# MCU.net
KiCad netlist of a schematic drawn in Altium Designer
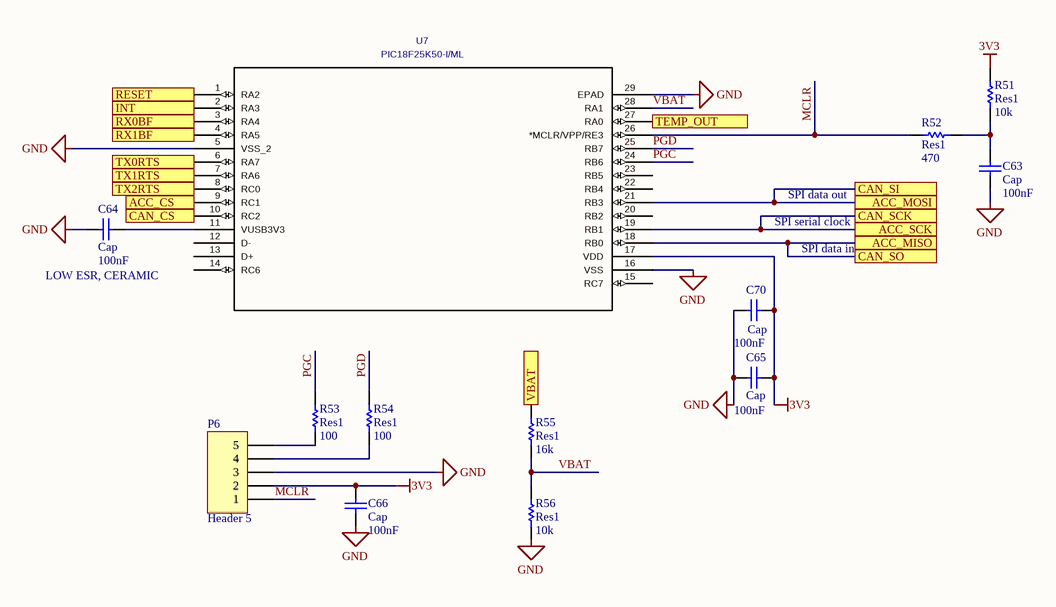
[diagram p0: MCU.SchDoc]

(export (version "E")
  (design (tool "Eeschema 10.0.6"))
  (components
    (comp (ref "C63")
      (value "Cap")
      (footprint "0402-A")
      (description "Capacitor")
      (fields (field (name "ALTIUM_VALUE") "100nF") (field (name "PUBLISHER") "Altium Limited"))
      (libsource (lib "Miscellaneous Devices") (part "Cap"))
    )
    (comp (ref "C64")
      (value "Cap")
      (footprint "0402-A")
      (description "Capacitor")
      (fields (field (name "ALTIUM_VALUE") "100nF") (field (name "PUBLISHER") "Altium Limited"))
      (libsource (lib "Miscellaneous Devices") (part "Cap"))
    )
    (comp (ref "C65")
      (value "Cap")
      (footprint "0402-A")
      (description "Capacitor")
      (fields (field (name "ALTIUM_VALUE") "100nF") (field (name "PUBLISHER") "Altium Limited"))
      (libsource (lib "Miscellaneous Devices") (part "Cap"))
    )
    (comp (ref "C66")
      (value "Cap")
      (footprint "0402-A")
      (description "Capacitor")
      (fields (field (name "ALTIUM_VALUE") "100nF") (field (name "PUBLISHER") "Altium Limited"))
      (libsource (lib "Miscellaneous Devices") (part "Cap"))
    )
    (comp (ref "C70")
      (value "Cap")
      (footprint "0402-A")
      (description "Capacitor")
      (fields (field (name "ALTIUM_VALUE") "100nF") (field (name "PUBLISHER") "Altium Limited"))
      (libsource (lib "Miscellaneous Devices") (part "Cap"))
    )
    (comp (ref "P6")
      (value "Header 5")
      (footprint "HDR1X5")
      (description "Header, 5-Pin")
      (fields (field (name "PUBLISHER") "Altium Limited"))
      (libsource (lib "Miscellaneous Connectors") (part "Header 5"))
    )
    (comp (ref "R51")
      (value "Res1")
      (footprint "0402-A")
      (description "Resistor")
      (fields (field (name "ALTIUM_VALUE") "10k") (field (name "PUBLISHER") "Altium Limited"))
      (libsource (lib "Miscellaneous Devices") (part "Res1"))
    )
    (comp (ref "R52")
      (value "Res1")
      (footprint "0402-A")
      (description "Resistor")
      (fields (field (name "ALTIUM_VALUE") "470") (field (name "PUBLISHER") "Altium Limited"))
      (libsource (lib "Miscellaneous Devices") (part "Res1"))
    )
    (comp (ref "R53")
      (value "Res1")
      (footprint "0402-A")
      (description "Resistor")
      (fields (field (name "ALTIUM_VALUE") "100") (field (name "PUBLISHER") "Altium Limited"))
      (libsource (lib "Miscellaneous Devices") (part "Res1"))
    )
    (comp (ref "R54")
      (value "Res1")
      (footprint "0402-A")
      (description "Resistor")
      (fields (field (name "ALTIUM_VALUE") "100") (field (name "PUBLISHER") "Altium Limited"))
      (libsource (lib "Miscellaneous Devices") (part "Res1"))
    )
    (comp (ref "R55")
      (value "Res1")
      (footprint "0402-A")
      (description "Resistor")
      (fields (field (name "ALTIUM_VALUE") "16k") (field (name "PUBLISHER") "Altium Limited"))
      (libsource (lib "Miscellaneous Devices") (part "Res1"))
    )
    (comp (ref "R56")
      (value "Res1")
      (footprint "0402-A")
      (description "Resistor")
      (fields (field (name "ALTIUM_VALUE") "10k") (field (name "PUBLISHER") "Altium Limited"))
      (libsource (lib "Miscellaneous Devices") (part "Res1"))
    )
    (comp (ref "U7")
      (value "PIC18F25K50-I/ML")
      (footprint "QFN28_6X6MC_MCH")
      (libsource (lib "PIC18F25K50IML") (part "PIC18F25K50-I/ML"))
    )
  )
  (nets
    (net (code "1") (name "/ACC_CS") (class "Default")
      (node (ref "U7") (pin "9") (pinfunction "RC1_9") (pintype "bidirectional"))
    )
    (net (code "2") (name "/ACC_MISO") (class "Default")
      (node (ref "U7") (pin "18") (pinfunction "RB0_18") (pintype "bidirectional"))
    )
    (net (code "3") (name "/ACC_MOSI") (class "Default")
      (node (ref "U7") (pin "21") (pinfunction "RB3_21") (pintype "bidirectional"))
    )
    (net (code "4") (name "/ACC_SCK") (class "Default")
      (node (ref "U7") (pin "19") (pinfunction "RB1_19") (pintype "bidirectional"))
    )
    (net (code "5") (name "/CAN_CS") (class "Default")
      (node (ref "U7") (pin "10") (pinfunction "RC2_10") (pintype "bidirectional"))
    )
    (net (code "6") (name "/INT") (class "Default")
      (node (ref "U7") (pin "2") (pinfunction "RA3_2") (pintype "bidirectional"))
    )
    (net (code "7") (name "/MCLR") (class "Default")
      (node (ref "P6") (pin "1") (pinfunction "1_1") (pintype "passive"))
      (node (ref "R52") (pin "2") (pinfunction "2_2") (pintype "passive"))
      (node (ref "U7") (pin "26") (pinfunction "*MCLR/VPP/RE3_26") (pintype "bidirectional"))
    )
    (net (code "8") (name "/PGC") (class "Default")
      (node (ref "R53") (pin "2") (pinfunction "2_2") (pintype "passive"))
      (node (ref "U7") (pin "24") (pinfunction "RB6_24") (pintype "bidirectional"))
    )
    (net (code "9") (name "/PGD") (class "Default")
      (node (ref "R54") (pin "2") (pinfunction "2_2") (pintype "passive"))
      (node (ref "U7") (pin "25") (pinfunction "RB7_25") (pintype "bidirectional"))
    )
    (net (code "10") (name "/RESET") (class "Default")
      (node (ref "U7") (pin "1") (pinfunction "RA2_1") (pintype "bidirectional"))
    )
    (net (code "11") (name "/RX0BF") (class "Default")
      (node (ref "U7") (pin "3") (pinfunction "RA4_3") (pintype "bidirectional"))
    )
    (net (code "12") (name "/RX1BF") (class "Default")
      (node (ref "U7") (pin "4") (pinfunction "RA5_4") (pintype "bidirectional"))
    )
    (net (code "13") (name "/TEMP_OUT") (class "Default")
      (node (ref "U7") (pin "27") (pinfunction "RA0_27") (pintype "bidirectional"))
    )
    (net (code "14") (name "/TX0RTS") (class "Default")
      (node (ref "U7") (pin "6") (pinfunction "RA7_6") (pintype "bidirectional"))
    )
    (net (code "15") (name "/TX1RTS") (class "Default")
      (node (ref "U7") (pin "7") (pinfunction "RA6_7") (pintype "bidirectional"))
    )
    (net (code "16") (name "/TX2RTS") (class "Default")
      (node (ref "U7") (pin "8") (pinfunction "RC0_8") (pintype "bidirectional"))
    )
    (net (code "17") (name "/VBAT") (class "Default")
      (node (ref "R55") (pin "1") (pinfunction "1_1") (pintype "passive"))
      (node (ref "R56") (pin "2") (pinfunction "2_2") (pintype "passive"))
      (node (ref "U7") (pin "28") (pinfunction "RA1_28") (pintype "bidirectional"))
    )
    (net (code "18") (name "3V3") (class "Default")
      (node (ref "C65") (pin "2") (pinfunction "2_2") (pintype "passive"))
      (node (ref "C66") (pin "2") (pinfunction "2_2") (pintype "passive"))
      (node (ref "C70") (pin "2") (pinfunction "2_2") (pintype "passive"))
      (node (ref "P6") (pin "2") (pinfunction "2_2") (pintype "passive"))
      (node (ref "R51") (pin "2") (pinfunction "2_2") (pintype "passive"))
      (node (ref "U7") (pin "17") (pinfunction "VDD_17") (pintype "power_in"))
    )
    (net (code "19") (name "GND") (class "Default")
      (node (ref "C63") (pin "1") (pinfunction "1_1") (pintype "passive"))
      (node (ref "C64") (pin "1") (pinfunction "1_1") (pintype "passive"))
      (node (ref "C65") (pin "1") (pinfunction "1_1") (pintype "passive"))
      (node (ref "C66") (pin "1") (pinfunction "1_1") (pintype "passive"))
      (node (ref "C70") (pin "1") (pinfunction "1_1") (pintype "passive"))
      (node (ref "P6") (pin "3") (pinfunction "3_3") (pintype "passive"))
      (node (ref "R56") (pin "1") (pinfunction "1_1") (pintype "passive"))
      (node (ref "U7") (pin "16") (pinfunction "VSS_16") (pintype "power_in"))
      (node (ref "U7") (pin "29") (pinfunction "EPAD_29") (pintype "passive"))
      (node (ref "U7") (pin "5") (pinfunction "VSS_2_5") (pintype "power_in"))
    )
    (net (code "20") (name "Net-(C63-Pad2)") (class "Default")
      (node (ref "C63") (pin "2") (pinfunction "2_2") (pintype "passive"))
      (node (ref "R51") (pin "1") (pinfunction "1_1") (pintype "passive"))
      (node (ref "R52") (pin "1") (pinfunction "1_1") (pintype "passive"))
    )
    (net (code "21") (name "Net-(P6-Pad4)") (class "Default")
      (node (ref "P6") (pin "4") (pinfunction "4_4") (pintype "passive"))
      (node (ref "R54") (pin "1") (pinfunction "1_1") (pintype "passive"))
    )
    (net (code "22") (name "Net-(P6-Pad5)") (class "Default")
      (node (ref "P6") (pin "5") (pinfunction "5_5") (pintype "passive"))
      (node (ref "R53") (pin "1") (pinfunction "1_1") (pintype "passive"))
    )
    (net (code "23") (name "Net-(U7-VUSB3V3)") (class "Default")
      (node (ref "C64") (pin "2") (pinfunction "2_2") (pintype "passive"))
      (node (ref "U7") (pin "11") (pinfunction "VUSB3V3_11") (pintype "power_in"))
    )
    (net (code "24") (name "unconnected-(R55-Pad2)") (class "Default")
      (node (ref "R55") (pin "2") (pinfunction "2_2") (pintype "passive"))
    )
    (net (code "25") (name "unconnected-(U7-D+-Pad13)") (class "Default")
      (node (ref "U7") (pin "13") (pinfunction "D+_13") (pintype "passive"))
    )
    (net (code "26") (name "unconnected-(U7-D--Pad12)") (class "Default")
      (node (ref "U7") (pin "12") (pinfunction "D-_12") (pintype "passive"))
    )
    (net (code "27") (name "unconnected-(U7-RB2-Pad20)") (class "Default")
      (node (ref "U7") (pin "20") (pinfunction "RB2_20") (pintype "bidirectional"))
    )
    (net (code "28") (name "unconnected-(U7-RB4-Pad22)") (class "Default")
      (node (ref "U7") (pin "22") (pinfunction "RB4_22") (pintype "bidirectional"))
    )
    (net (code "29") (name "unconnected-(U7-RB5-Pad23)") (class "Default")
      (node (ref "U7") (pin "23") (pinfunction "RB5_23") (pintype "bidirectional"))
    )
    (net (code "30") (name "unconnected-(U7-RC6-Pad14)") (class "Default")
      (node (ref "U7") (pin "14") (pinfunction "RC6_14") (pintype "bidirectional"))
    )
    (net (code "31") (name "unconnected-(U7-RC7-Pad15)") (class "Default")
      (node (ref "U7") (pin "15") (pinfunction "RC7_15") (pintype "bidirectional"))
    )
  )
)
